# School_Vn_project.net
KiCad netlist of a schematic drawn in EasyEDA Pro
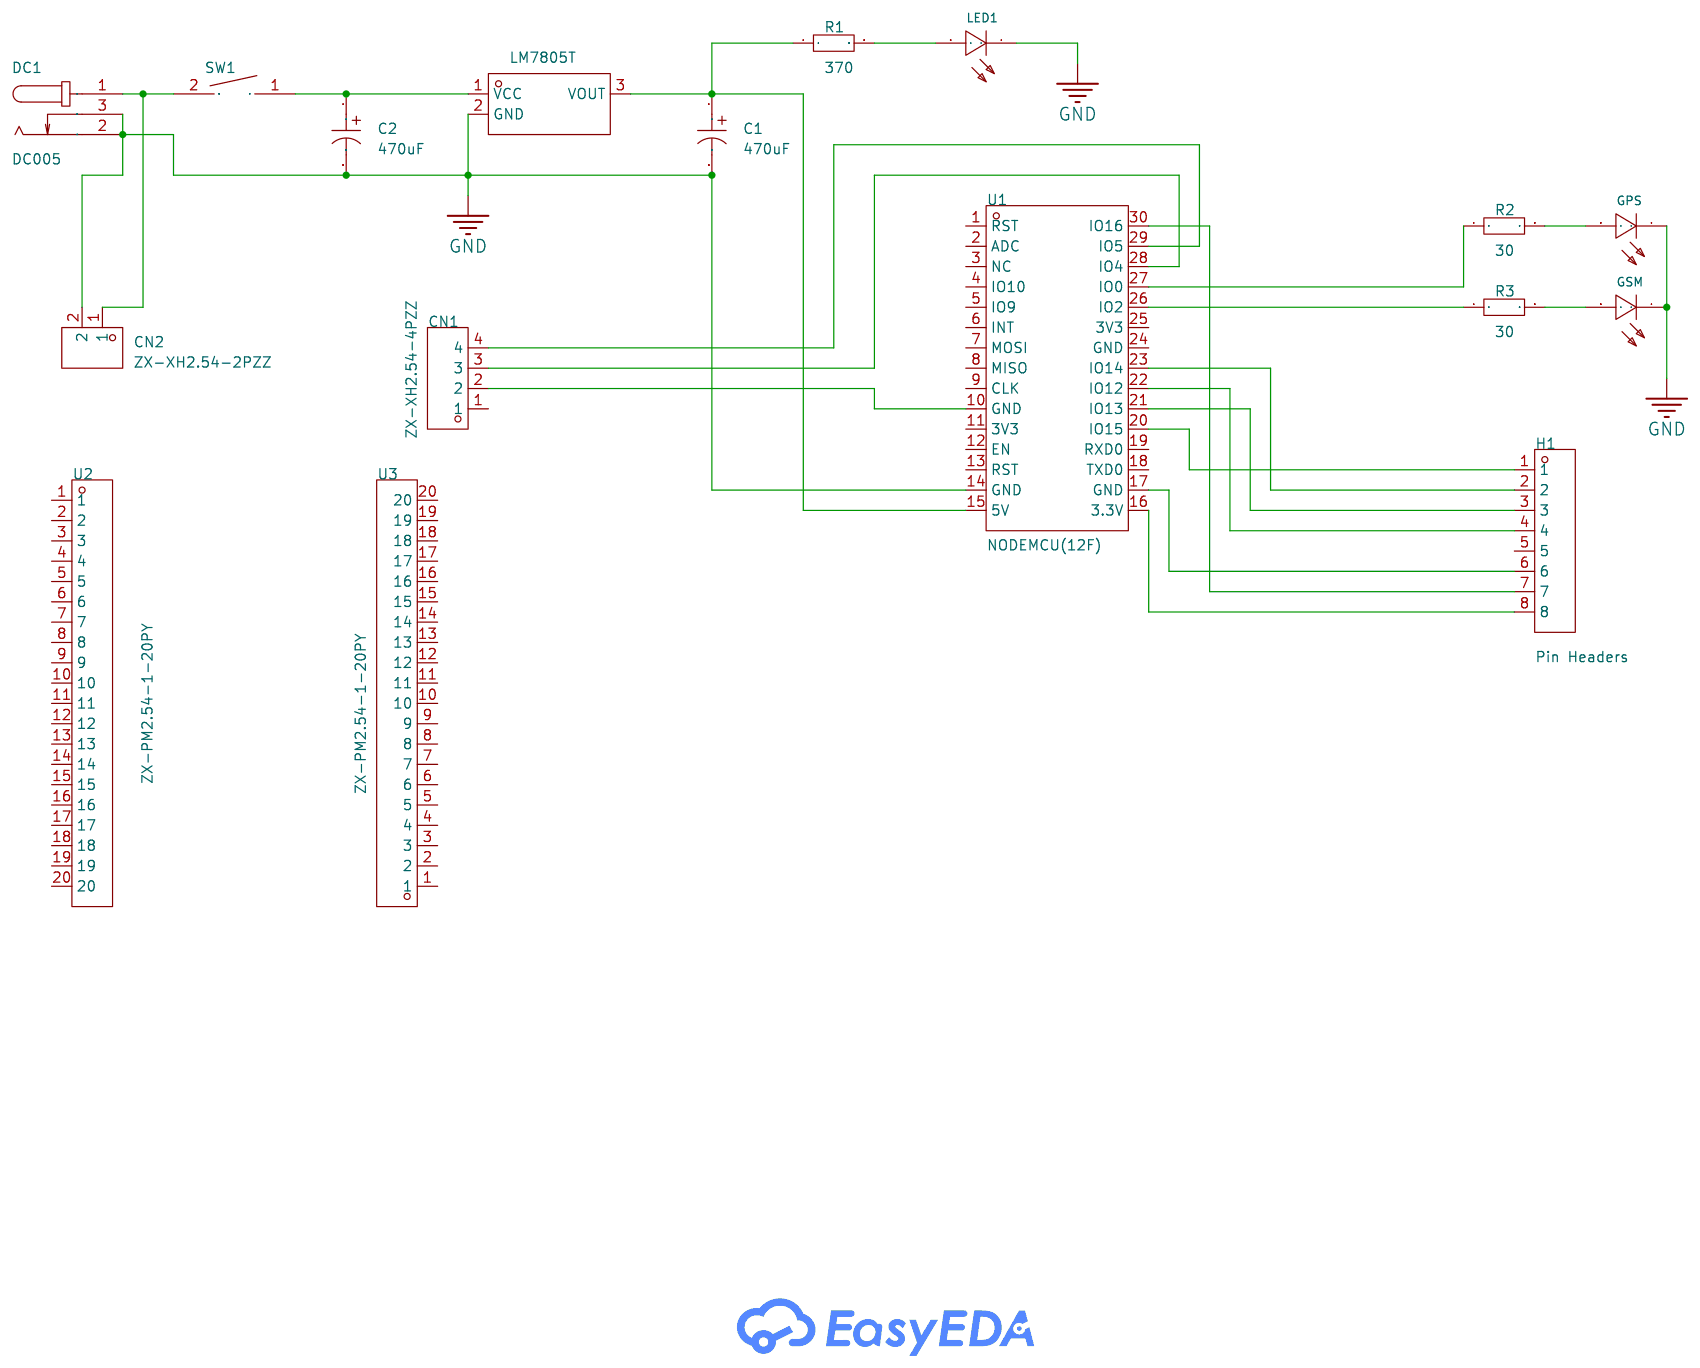
[diagram p0: schematic sheet]

(export (version "E")
  (design (tool "Eeschema 10.0.6"))
  (components
    (comp (ref "7805T")
      (value "LM7805T")
      (footprint "easyedapro:TO-220-3_L10.1-W4.7-P2.54-L")
      (fields (field (name "Manufacturer") "HGSEMI(华冠)"))
      (libsource (lib "easyedapro") (part "LM7805T_C7432180"))
    )
    (comp (ref "C1")
      (value "470uF")
      (footprint "easyedapro:CAP-TH_BD8.0-P3.50-D0.5-FD")
      (fields (field (name "Manufacturer Part") "16V470uF CD110") (field (name "Manufacturer") "HRK(鸿瑞凯电子)"))
      (libsource (lib "easyedapro") (part "16V470UF CD110"))
    )
    (comp (ref "C2")
      (value "470uF")
      (footprint "easyedapro:CAP-TH_BD8.0-P3.50-D0.5-FD")
      (fields (field (name "Manufacturer Part") "16V470uF CD110") (field (name "Manufacturer") "HRK(鸿瑞凯电子)"))
      (libsource (lib "easyedapro") (part "16V470UF CD110"))
    )
    (comp (ref "CN1")
      (value "ZX-XH2.54-4PZZ")
      (footprint "easyedapro:CONN-TH_4P-P2.50_4PIN")
      (fields (field (name "Manufacturer") "Megastar(兆星)"))
      (libsource (lib "easyedapro") (part "ZX-XH2.54-4PZZ"))
    )
    (comp (ref "CN2")
      (value "ZX-XH2.54-2PZZ")
      (footprint "easyedapro:CONN-TH_2P-P2.50_HX25003-2A")
      (fields (field (name "Manufacturer") "Megastar(兆星)"))
      (libsource (lib "easyedapro") (part "ZX-XH2.54-2PZZ"))
    )
    (comp (ref "DC1")
      (value "DC005")
      (footprint "easyedapro:DC-IN-TH_DC005")
      (fields (field (name "Manufacturer") "SHOU HAN(首韩)"))
      (libsource (lib "easyedapro") (part "DC005_C431533"))
    )
    (comp (ref "GPS")
      (value "NCD0603R1")
      (footprint "easyedapro:LED0603-RD_RED")
      (fields (field (name "Manufacturer") "国星光电"))
      (libsource (lib "easyedapro") (part "FC-DA1608HRK-620D"))
    )
    (comp (ref "GSM")
      (value "NCD0603R1")
      (footprint "easyedapro:LED0603-RD_RED")
      (fields (field (name "Manufacturer") "国星光电"))
      (libsource (lib "easyedapro") (part "FC-DA1608HRK-620D"))
    )
    (comp (ref "H1")
      (value "Pin Headers")
      (footprint "easyedapro:HDR-TH_8P-P2.54-V-M")
      (fields (field (name "Manufacturer") "XFCN(兴飞)"))
      (libsource (lib "easyedapro") (part "PZ254V-11-08P"))
    )
    (comp (ref "LED1")
      (value "NCD0603R1")
      (footprint "easyedapro:LED0603-RD_RED")
      (fields (field (name "Manufacturer") "国星光电"))
      (libsource (lib "easyedapro") (part "FC-DA1608HRK-620D"))
    )
    (comp (ref "R1") (value "370") (footprint "easyedapro:R0603") (libsource (lib "easyedapro") (part "Res")))
    (comp (ref "R2") (value "30") (footprint "easyedapro:R0603") (libsource (lib "easyedapro") (part "Res")))
    (comp (ref "R3") (value "30") (footprint "easyedapro:R0603") (libsource (lib "easyedapro") (part "Res")))
    (comp (ref "SW1")
      (value "RS601HL-1010011BB")
      (footprint "easyedapro:SW-TH_RS601HL-1010011BB")
      (fields (field (name "Manufacturer") "HCTL(华灿天禄)"))
      (libsource (lib "easyedapro") (part "RS601HL-1010011BB"))
    )
    (comp (ref "U1")
      (value "NODEMCU(12F)")
      (footprint "easyedapro:WIFIM-TH_NODEMCU-8266")
      (fields (field (name "Manufacturer") "Ai-Thinker(安信可)"))
      (libsource (lib "easyedapro") (part "NODEMCU(12F)"))
    )
    (comp (ref "U2")
      (value "ZX-PM2.54-1-20PY")
      (footprint "easyedapro:HDR-TH_20P-P2.54-V-F")
      (fields (field (name "Manufacturer") "Megastar(兆星)"))
      (libsource (lib "easyedapro") (part "ZX-PM2.54-1-20PY"))
    )
    (comp (ref "U3")
      (value "ZX-PM2.54-1-20PY")
      (footprint "easyedapro:HDR-TH_20P-P2.54-V-F")
      (fields (field (name "Manufacturer") "Megastar(兆星)"))
      (libsource (lib "easyedapro") (part "ZX-PM2.54-1-20PY"))
    )
  )
  (nets
    (net (code "1") (name "GND") (class "Default")
      (node (ref "7805T") (pin "2") (pinfunction "GND_2") (pintype "unspecified"))
      (node (ref "C1") (pin "2") (pinfunction "2_2") (pintype "input"))
      (node (ref "C2") (pin "2") (pinfunction "2_2") (pintype "input"))
      (node (ref "CN2") (pin "2") (pinfunction "2_2") (pintype "unspecified"))
      (node (ref "DC1") (pin "2") (pinfunction "2_2") (pintype "unspecified"))
      (node (ref "DC1") (pin "3") (pinfunction "3_3") (pintype "unspecified"))
      (node (ref "GPS") (pin "1") (pinfunction "K_1") (pintype "input"))
      (node (ref "GSM") (pin "1") (pinfunction "K_1") (pintype "input"))
      (node (ref "LED1") (pin "1") (pinfunction "K_1") (pintype "input"))
      (node (ref "U1") (pin "14") (pinfunction "GND_14") (pintype "unspecified"))
    )
    (net (code "2") (name "Net-(7805T-VCC)") (class "Default")
      (node (ref "7805T") (pin "1") (pinfunction "VCC_1") (pintype "unspecified"))
      (node (ref "C2") (pin "1") (pinfunction "1_1") (pintype "input"))
      (node (ref "SW1") (pin "1") (pinfunction "1_1") (pintype "input"))
    )
    (net (code "3") (name "Net-(7805T-VOUT)") (class "Default")
      (node (ref "7805T") (pin "3") (pinfunction "VOUT_3") (pintype "unspecified"))
      (node (ref "C1") (pin "1") (pinfunction "1_1") (pintype "input"))
      (node (ref "R1") (pin "1") (pinfunction "1_1") (pintype "input"))
      (node (ref "U1") (pin "15") (pinfunction "5V_15") (pintype "unspecified"))
    )
    (net (code "4") (name "Net-(CN1-Pad2)") (class "Default")
      (node (ref "CN1") (pin "2") (pinfunction "2_2") (pintype "unspecified"))
      (node (ref "U1") (pin "10") (pinfunction "GND_10") (pintype "unspecified"))
    )
    (net (code "5") (name "Net-(CN2-Pad1)") (class "Default")
      (node (ref "CN2") (pin "1") (pinfunction "1_1") (pintype "unspecified"))
      (node (ref "DC1") (pin "1") (pinfunction "1_1") (pintype "unspecified"))
      (node (ref "SW1") (pin "2") (pinfunction "2_2") (pintype "input"))
    )
    (net (code "6") (name "Net-(GPS-A)") (class "Default")
      (node (ref "GPS") (pin "2") (pinfunction "A_2") (pintype "input"))
      (node (ref "R2") (pin "2") (pinfunction "2_2") (pintype "input"))
    )
    (net (code "7") (name "Net-(GSM-A)") (class "Default")
      (node (ref "GSM") (pin "2") (pinfunction "A_2") (pintype "input"))
      (node (ref "R3") (pin "2") (pinfunction "2_2") (pintype "input"))
    )
    (net (code "8") (name "Net-(H1-Pad6)") (class "Default")
      (node (ref "H1") (pin "6") (pinfunction "6_6") (pintype "unspecified"))
      (node (ref "U1") (pin "17") (pinfunction "GND_17") (pintype "unspecified"))
    )
    (net (code "9") (name "Net-(LED1-A)") (class "Default")
      (node (ref "LED1") (pin "2") (pinfunction "A_2") (pintype "input"))
      (node (ref "R1") (pin "2") (pinfunction "2_2") (pintype "input"))
    )
    (net (code "10") (name "Net-(U1-3.3V)") (class "Default")
      (node (ref "H1") (pin "8") (pinfunction "8_8") (pintype "unspecified"))
      (node (ref "U1") (pin "16") (pinfunction "3.3V_16") (pintype "unspecified"))
    )
    (net (code "11") (name "Net-(U1-IO0)") (class "Default")
      (node (ref "R2") (pin "1") (pinfunction "1_1") (pintype "input"))
      (node (ref "U1") (pin "27") (pinfunction "IO0_27") (pintype "unspecified"))
    )
    (net (code "12") (name "Net-(U1-IO2)") (class "Default")
      (node (ref "R3") (pin "1") (pinfunction "1_1") (pintype "input"))
      (node (ref "U1") (pin "26") (pinfunction "IO2_26") (pintype "unspecified"))
    )
    (net (code "13") (name "Net-(U1-IO4)") (class "Default")
      (node (ref "CN1") (pin "3") (pinfunction "3_3") (pintype "unspecified"))
      (node (ref "U1") (pin "28") (pinfunction "IO4_28") (pintype "unspecified"))
    )
    (net (code "14") (name "Net-(U1-IO5)") (class "Default")
      (node (ref "CN1") (pin "4") (pinfunction "4_4") (pintype "unspecified"))
      (node (ref "U1") (pin "29") (pinfunction "IO5_29") (pintype "unspecified"))
    )
    (net (code "15") (name "Net-(U1-IO12)") (class "Default")
      (node (ref "H1") (pin "4") (pinfunction "4_4") (pintype "unspecified"))
      (node (ref "U1") (pin "22") (pinfunction "IO12_22") (pintype "unspecified"))
    )
    (net (code "16") (name "Net-(U1-IO13)") (class "Default")
      (node (ref "H1") (pin "3") (pinfunction "3_3") (pintype "unspecified"))
      (node (ref "U1") (pin "21") (pinfunction "IO13_21") (pintype "unspecified"))
    )
    (net (code "17") (name "Net-(U1-IO14)") (class "Default")
      (node (ref "H1") (pin "2") (pinfunction "2_2") (pintype "unspecified"))
      (node (ref "U1") (pin "23") (pinfunction "IO14_23") (pintype "unspecified"))
    )
    (net (code "18") (name "Net-(U1-IO15)") (class "Default")
      (node (ref "H1") (pin "1") (pinfunction "1_1") (pintype "unspecified"))
      (node (ref "U1") (pin "20") (pinfunction "IO15_20") (pintype "unspecified"))
    )
    (net (code "19") (name "Net-(U1-IO16)") (class "Default")
      (node (ref "H1") (pin "7") (pinfunction "7_7") (pintype "unspecified"))
      (node (ref "U1") (pin "30") (pinfunction "IO16_30") (pintype "unspecified"))
    )
    (net (code "20") (name "unconnected-(CN1-Pad1)") (class "Default")
      (node (ref "CN1") (pin "1") (pinfunction "1_1") (pintype "unspecified"))
    )
    (net (code "21") (name "unconnected-(H1-Pad5)") (class "Default")
      (node (ref "H1") (pin "5") (pinfunction "5_5") (pintype "unspecified"))
    )
    (net (code "22") (name "unconnected-(U1-3V3-Pad11)") (class "Default")
      (node (ref "U1") (pin "11") (pinfunction "3V3_11") (pintype "unspecified"))
    )
    (net (code "23") (name "unconnected-(U1-3V3-Pad25)") (class "Default")
      (node (ref "U1") (pin "25") (pinfunction "3V3_25") (pintype "unspecified"))
    )
    (net (code "24") (name "unconnected-(U1-ADC-Pad2)") (class "Default")
      (node (ref "U1") (pin "2") (pinfunction "ADC_2") (pintype "unspecified"))
    )
    (net (code "25") (name "unconnected-(U1-CLK-Pad9)") (class "Default")
      (node (ref "U1") (pin "9") (pinfunction "CLK_9") (pintype "unspecified"))
    )
    (net (code "26") (name "unconnected-(U1-EN-Pad12)") (class "Default")
      (node (ref "U1") (pin "12") (pinfunction "EN_12") (pintype "unspecified"))
    )
    (net (code "27") (name "unconnected-(U1-GND-Pad24)") (class "Default")
      (node (ref "U1") (pin "24") (pinfunction "GND_24") (pintype "unspecified"))
    )
    (net (code "28") (name "unconnected-(U1-INT-Pad6)") (class "Default")
      (node (ref "U1") (pin "6") (pinfunction "INT_6") (pintype "unspecified"))
    )
    (net (code "29") (name "unconnected-(U1-IO9-Pad5)") (class "Default")
      (node (ref "U1") (pin "5") (pinfunction "IO9_5") (pintype "unspecified"))
    )
    (net (code "30") (name "unconnected-(U1-IO10-Pad4)") (class "Default")
      (node (ref "U1") (pin "4") (pinfunction "IO10_4") (pintype "unspecified"))
    )
    (net (code "31") (name "unconnected-(U1-MISO-Pad8)") (class "Default")
      (node (ref "U1") (pin "8") (pinfunction "MISO_8") (pintype "unspecified"))
    )
    (net (code "32") (name "unconnected-(U1-MOSI-Pad7)") (class "Default")
      (node (ref "U1") (pin "7") (pinfunction "MOSI_7") (pintype "unspecified"))
    )
    (net (code "33") (name "unconnected-(U1-NC-Pad3)") (class "Default")
      (node (ref "U1") (pin "3") (pinfunction "NC_3") (pintype "unspecified"))
    )
    (net (code "34") (name "unconnected-(U1-RST-Pad1)") (class "Default")
      (node (ref "U1") (pin "1") (pinfunction "RST_1") (pintype "unspecified"))
    )
    (net (code "35") (name "unconnected-(U1-RST-Pad13)") (class "Default")
      (node (ref "U1") (pin "13") (pinfunction "RST_13") (pintype "unspecified"))
    )
    (net (code "36") (name "unconnected-(U1-RXD0-Pad19)") (class "Default")
      (node (ref "U1") (pin "19") (pinfunction "RXD0_19") (pintype "unspecified"))
    )
    (net (code "37") (name "unconnected-(U1-TXD0-Pad18)") (class "Default")
      (node (ref "U1") (pin "18") (pinfunction "TXD0_18") (pintype "unspecified"))
    )
    (net (code "38") (name "unconnected-(U2-Pad1)") (class "Default")
      (node (ref "U2") (pin "1") (pinfunction "1_1") (pintype "unspecified"))
    )
    (net (code "39") (name "unconnected-(U2-Pad2)") (class "Default")
      (node (ref "U2") (pin "2") (pinfunction "2_2") (pintype "unspecified"))
    )
    (net (code "40") (name "unconnected-(U2-Pad3)") (class "Default")
      (node (ref "U2") (pin "3") (pinfunction "3_3") (pintype "unspecified"))
    )
    (net (code "41") (name "unconnected-(U2-Pad4)") (class "Default")
      (node (ref "U2") (pin "4") (pinfunction "4_4") (pintype "unspecified"))
    )
    (net (code "42") (name "unconnected-(U2-Pad5)") (class "Default")
      (node (ref "U2") (pin "5") (pinfunction "5_5") (pintype "unspecified"))
    )
    (net (code "43") (name "unconnected-(U2-Pad6)") (class "Default")
      (node (ref "U2") (pin "6") (pinfunction "6_6") (pintype "unspecified"))
    )
    (net (code "44") (name "unconnected-(U2-Pad7)") (class "Default")
      (node (ref "U2") (pin "7") (pinfunction "7_7") (pintype "unspecified"))
    )
    (net (code "45") (name "unconnected-(U2-Pad8)") (class "Default")
      (node (ref "U2") (pin "8") (pinfunction "8_8") (pintype "unspecified"))
    )
    (net (code "46") (name "unconnected-(U2-Pad9)") (class "Default")
      (node (ref "U2") (pin "9") (pinfunction "9_9") (pintype "unspecified"))
    )
    (net (code "47") (name "unconnected-(U2-Pad10)") (class "Default")
      (node (ref "U2") (pin "10") (pinfunction "10_10") (pintype "unspecified"))
    )
    (net (code "48") (name "unconnected-(U2-Pad11)") (class "Default")
      (node (ref "U2") (pin "11") (pinfunction "11_11") (pintype "unspecified"))
    )
    (net (code "49") (name "unconnected-(U2-Pad12)") (class "Default")
      (node (ref "U2") (pin "12") (pinfunction "12_12") (pintype "unspecified"))
    )
    (net (code "50") (name "unconnected-(U2-Pad13)") (class "Default")
      (node (ref "U2") (pin "13") (pinfunction "13_13") (pintype "unspecified"))
    )
    (net (code "51") (name "unconnected-(U2-Pad14)") (class "Default")
      (node (ref "U2") (pin "14") (pinfunction "14_14") (pintype "unspecified"))
    )
    (net (code "52") (name "unconnected-(U2-Pad15)") (class "Default")
      (node (ref "U2") (pin "15") (pinfunction "15_15") (pintype "unspecified"))
    )
    (net (code "53") (name "unconnected-(U2-Pad16)") (class "Default")
      (node (ref "U2") (pin "16") (pinfunction "16_16") (pintype "unspecified"))
    )
    (net (code "54") (name "unconnected-(U2-Pad17)") (class "Default")
      (node (ref "U2") (pin "17") (pinfunction "17_17") (pintype "unspecified"))
    )
    (net (code "55") (name "unconnected-(U2-Pad18)") (class "Default")
      (node (ref "U2") (pin "18") (pinfunction "18_18") (pintype "unspecified"))
    )
    (net (code "56") (name "unconnected-(U2-Pad19)") (class "Default")
      (node (ref "U2") (pin "19") (pinfunction "19_19") (pintype "unspecified"))
    )
    (net (code "57") (name "unconnected-(U2-Pad20)") (class "Default")
      (node (ref "U2") (pin "20") (pinfunction "20_20") (pintype "unspecified"))
    )
    (net (code "58") (name "unconnected-(U3-Pad1)") (class "Default")
      (node (ref "U3") (pin "1") (pinfunction "1_1") (pintype "unspecified"))
    )
    (net (code "59") (name "unconnected-(U3-Pad2)") (class "Default")
      (node (ref "U3") (pin "2") (pinfunction "2_2") (pintype "unspecified"))
    )
    (net (code "60") (name "unconnected-(U3-Pad3)") (class "Default")
      (node (ref "U3") (pin "3") (pinfunction "3_3") (pintype "unspecified"))
    )
    (net (code "61") (name "unconnected-(U3-Pad4)") (class "Default")
      (node (ref "U3") (pin "4") (pinfunction "4_4") (pintype "unspecified"))
    )
    (net (code "62") (name "unconnected-(U3-Pad5)") (class "Default")
      (node (ref "U3") (pin "5") (pinfunction "5_5") (pintype "unspecified"))
    )
    (net (code "63") (name "unconnected-(U3-Pad6)") (class "Default")
      (node (ref "U3") (pin "6") (pinfunction "6_6") (pintype "unspecified"))
    )
    (net (code "64") (name "unconnected-(U3-Pad7)") (class "Default")
      (node (ref "U3") (pin "7") (pinfunction "7_7") (pintype "unspecified"))
    )
    (net (code "65") (name "unconnected-(U3-Pad8)") (class "Default")
      (node (ref "U3") (pin "8") (pinfunction "8_8") (pintype "unspecified"))
    )
    (net (code "66") (name "unconnected-(U3-Pad9)") (class "Default")
      (node (ref "U3") (pin "9") (pinfunction "9_9") (pintype "unspecified"))
    )
    (net (code "67") (name "unconnected-(U3-Pad10)") (class "Default")
      (node (ref "U3") (pin "10") (pinfunction "10_10") (pintype "unspecified"))
    )
    (net (code "68") (name "unconnected-(U3-Pad11)") (class "Default")
      (node (ref "U3") (pin "11") (pinfunction "11_11") (pintype "unspecified"))
    )
    (net (code "69") (name "unconnected-(U3-Pad12)") (class "Default")
      (node (ref "U3") (pin "12") (pinfunction "12_12") (pintype "unspecified"))
    )
    (net (code "70") (name "unconnected-(U3-Pad13)") (class "Default")
      (node (ref "U3") (pin "13") (pinfunction "13_13") (pintype "unspecified"))
    )
    (net (code "71") (name "unconnected-(U3-Pad14)") (class "Default")
      (node (ref "U3") (pin "14") (pinfunction "14_14") (pintype "unspecified"))
    )
    (net (code "72") (name "unconnected-(U3-Pad15)") (class "Default")
      (node (ref "U3") (pin "15") (pinfunction "15_15") (pintype "unspecified"))
    )
    (net (code "73") (name "unconnected-(U3-Pad16)") (class "Default")
      (node (ref "U3") (pin "16") (pinfunction "16_16") (pintype "unspecified"))
    )
    (net (code "74") (name "unconnected-(U3-Pad17)") (class "Default")
      (node (ref "U3") (pin "17") (pinfunction "17_17") (pintype "unspecified"))
    )
    (net (code "75") (name "unconnected-(U3-Pad18)") (class "Default")
      (node (ref "U3") (pin "18") (pinfunction "18_18") (pintype "unspecified"))
    )
    (net (code "76") (name "unconnected-(U3-Pad19)") (class "Default")
      (node (ref "U3") (pin "19") (pinfunction "19_19") (pintype "unspecified"))
    )
    (net (code "77") (name "unconnected-(U3-Pad20)") (class "Default")
      (node (ref "U3") (pin "20") (pinfunction "20_20") (pintype "unspecified"))
    )
  )
)
